# 2015_ALIM_HITEC.net
KiCad netlist of a schematic drawn in Altium Designer
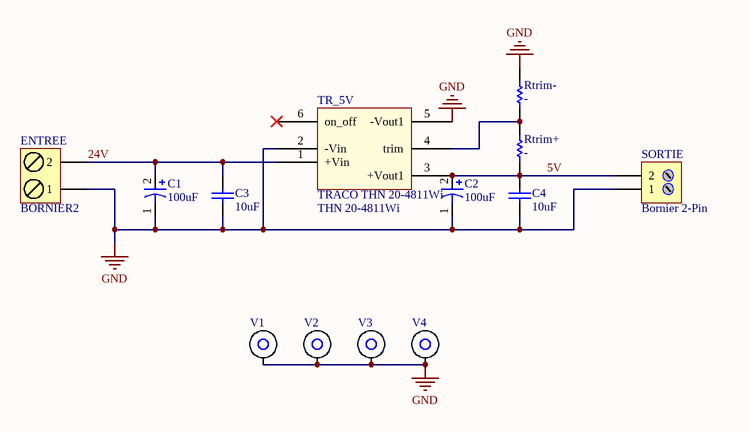
[diagram p0: 2015_ALIM_HITEC.SchDoc]

(export (version "E")
  (design (tool "Eeschema 10.0.6"))
  (components
    (comp (ref "C1")
      (value "100uF")
      (footprint "CONDENSATEUR_POLARISE_ELECTROLYTIQUE_RADIAL_5.08/8.9")
      (description "Polarized Capacitor")
      (libsource (lib "_ROBOT") (part "Condensateur Polarise Traversant"))
    )
    (comp (ref "C2")
      (value "100uF")
      (footprint "CONDENSATEUR_POLARISE_ELECTROLYTIQUE_RADIAL_5.08/8.9")
      (description "Polarized Capacitor")
      (libsource (lib "_ROBOT") (part "Condensateur Polarise Traversant"))
    )
    (comp (ref "C3")
      (value "10uF")
      (footprint "C1206_N")
      (description "Capacitor")
      (fields (field (name "PUBLISHER") "Altium Limited"))
      (libsource (lib "DG_Condensateur") (part "Capacitor"))
    )
    (comp (ref "C4")
      (value "10uF")
      (footprint "C1206_N")
      (description "Capacitor")
      (fields (field (name "PUBLISHER") "Altium Limited"))
      (libsource (lib "DG_Condensateur") (part "Capacitor"))
    )
    (comp (ref "ENTREE")
      (value "BORNIER2")
      (footprint "BORNIER2_FEM_COUDE")
      (description "Terminal blocks, 2 pins, pitch=5mm")
      (libsource (lib "Robot2010") (part "BORNIER2"))
    )
    (comp (ref "Rtrim+")
      (value "-")
      (footprint "R1206_N")
      (description "Resistor")
      (fields (field (name "PUBLISHER") "Altium Limited"))
      (libsource (lib "_ROBOT") (part "Resistor"))
    )
    (comp (ref "Rtrim-")
      (value "-")
      (footprint "R1206_N")
      (description "Resistor")
      (fields (field (name "PUBLISHER") "Altium Limited"))
      (libsource (lib "_ROBOT") (part "Resistor"))
    )
    (comp (ref "SORTIE")
      (value "Bornier 2-Pin")
      (footprint "BORNIER2_HORIZ")
      (fields (field (name "PUBLISHER") "Altium Limited"))
      (libsource (lib "DG_Connecteur") (part "Bornier 2-Pin"))
    )
    (comp (ref "TR_5V")
      (value "TRACO THN 20-4811Wi")
      (footprint "TRACO_THN20")
      (description "Traco 20W 24V to 5V*4A")
      (fields (field (name "REF") "THN 20-4811Wi"))
      (libsource (lib "_ROBOT") (part "TRACO THN 20-4811Wi"))
    )
    (comp (ref "V1")
      (value "Entretoise WURTH CMS")
      (footprint "ENTRETOISE_CMS")
      (description "Entretoise Wurth")
      (fields (field (name "PUBLISHER") "Damien Guitton"))
      (libsource (lib "_ROBOT") (part "Entretoise WURTH CMS"))
    )
    (comp (ref "V2")
      (value "Entretoise WURTH CMS")
      (footprint "ENTRETOISE_CMS")
      (description "Entretoise Wurth")
      (fields (field (name "PUBLISHER") "Damien Guitton"))
      (libsource (lib "_ROBOT") (part "Entretoise WURTH CMS"))
    )
    (comp (ref "V3")
      (value "Entretoise WURTH CMS")
      (footprint "ENTRETOISE_CMS")
      (description "Entretoise Wurth")
      (fields (field (name "PUBLISHER") "Damien Guitton"))
      (libsource (lib "_ROBOT") (part "Entretoise WURTH CMS"))
    )
    (comp (ref "V4")
      (value "Entretoise WURTH CMS")
      (footprint "ENTRETOISE_CMS")
      (description "Entretoise Wurth")
      (fields (field (name "PUBLISHER") "Damien Guitton"))
      (libsource (lib "_ROBOT") (part "Entretoise WURTH CMS"))
    )
  )
  (nets
    (net (code "1") (name "/5V") (class "Default")
      (node (ref "C2") (pin "2") (pinfunction "2_2") (pintype "passive"))
      (node (ref "C4") (pin "2") (pinfunction "2_2") (pintype "passive"))
      (node (ref "Rtrim+") (pin "1") (pinfunction "1_1") (pintype "passive"))
      (node (ref "SORTIE") (pin "2") (pinfunction "2_2") (pintype "passive"))
      (node (ref "TR_5V") (pin "3") (pinfunction "+Vout1_3") (pintype "passive"))
    )
    (net (code "2") (name "/24V") (class "Default")
      (node (ref "C1") (pin "2") (pinfunction "2_2") (pintype "passive"))
      (node (ref "C3") (pin "2") (pinfunction "2_2") (pintype "passive"))
      (node (ref "ENTREE") (pin "2") (pinfunction "2_2") (pintype "passive"))
      (node (ref "TR_5V") (pin "1") (pinfunction "+Vin_1") (pintype "passive"))
    )
    (net (code "3") (name "GND") (class "Default")
      (node (ref "C1") (pin "1") (pinfunction "1_1") (pintype "passive"))
      (node (ref "C2") (pin "1") (pinfunction "1_1") (pintype "passive"))
      (node (ref "C3") (pin "1") (pinfunction "1_1") (pintype "passive"))
      (node (ref "C4") (pin "1") (pinfunction "1_1") (pintype "passive"))
      (node (ref "ENTREE") (pin "1") (pinfunction "1_1") (pintype "passive"))
      (node (ref "Rtrim-") (pin "2") (pinfunction "2_2") (pintype "passive"))
      (node (ref "SORTIE") (pin "1") (pinfunction "1_1") (pintype "passive"))
      (node (ref "TR_5V") (pin "2") (pinfunction "-Vin_2") (pintype "passive"))
      (node (ref "TR_5V") (pin "5") (pinfunction "-Vout1_5") (pintype "passive"))
      (node (ref "V1") (pin "1") (pinfunction "1_1") (pintype "passive"))
      (node (ref "V2") (pin "1") (pinfunction "1_1") (pintype "passive"))
      (node (ref "V3") (pin "1") (pinfunction "1_1") (pintype "passive"))
      (node (ref "V4") (pin "1") (pinfunction "1_1") (pintype "passive"))
    )
    (net (code "4") (name "Net-(TR_5V-trim)") (class "Default")
      (node (ref "Rtrim+") (pin "2") (pinfunction "2_2") (pintype "passive"))
      (node (ref "Rtrim-") (pin "1") (pinfunction "1_1") (pintype "passive"))
      (node (ref "TR_5V") (pin "4") (pinfunction "trim_4") (pintype "passive"))
    )
    (net (code "5") (name "unconnected-(TR_5V-on_off-Pad6)") (class "Default")
      (node (ref "TR_5V") (pin "6") (pinfunction "on_off_6") (pintype "passive+no_connect"))
    )
  )
)
